# RELAY16.net
KiCad netlist of a schematic drawn in Altium Designer
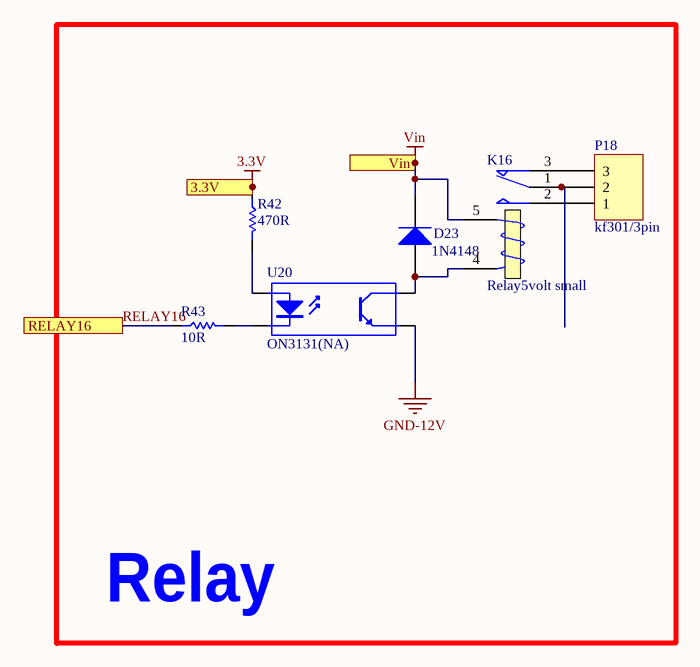
[diagram p0: RELAY16.SchDoc]

(export (version "E")
  (design (tool "Eeschema 10.0.6"))
  (components
    (comp (ref "D23")
      (value "1N4148")
      (footprint "sod123")
      (description "1 Amp General Purpose Rectifier")
      (fields (field (name "PUBLISHER") "Altium Limited"))
      (libsource (lib "Miscellaneous Devices") (part "Diode 1N4007"))
    )
    (comp (ref "K16")
      (value "Relay5volt small")
      (footprint "relay5_childern")
      (description "SPDT Relay")
      (fields (field (name "PUBLISHER") "Altium Limited"))
      (libsource (lib "FLIB") (part "Relay"))
    )
    (comp (ref "P18")
      (value "kf301/3pin")
      (footprint "Blue Connector 1*3 -kf301")
      (fields (field (name "PUBLISHER") "Altium Limited"))
      (libsource (lib "Miscellaneous Connectors") (part "Header 3"))
    )
    (comp (ref "R42")
      (value "470R")
      (footprint "0805/resistor")
      (description "Resistor")
      (fields (field (name "TOLERANCE") "5%") (field (name "POWER") "1/8 W"))
      (libsource (lib "skille") (part "Resistor"))
    )
    (comp (ref "R43")
      (value "10R")
      (footprint "0805/resistor")
      (description "Resistor")
      (fields (field (name "TOLERANCE") "5%") (field (name "POWER") "1/8 W"))
      (libsource (lib "skille") (part "Resistor"))
    )
    (comp (ref "U20")
      (value "ON3131(NA)")
      (footprint "OPTO_COUPLER")
      (description "4-Pin Phototransistor Optocoupler")
      (fields (field (name "PUBLISHER") "Altium Limited"))
      (libsource (lib "skille") (part "Optoisolator1"))
    )
  )
  (nets
    (net (code "1") (name "/RELAY16") (class "Default")
      (node (ref "R43") (pin "1") (pinfunction "1_1") (pintype "passive"))
    )
    (net (code "2") (name "3.3V") (class "Default")
      (node (ref "R42") (pin "1") (pinfunction "1_1") (pintype "passive"))
    )
    (net (code "3") (name "GND-12V") (class "Default")
      (node (ref "U20") (pin "3") (pinfunction "E_3") (pintype "passive"))
    )
    (net (code "4") (name "Net-(K16-COM)") (class "Default")
      (node (ref "K16") (pin "1") (pinfunction "COM_1") (pintype "passive"))
      (node (ref "P18") (pin "2") (pinfunction "2_2") (pintype "passive"))
    )
    (net (code "5") (name "Net-(K16-NO)") (class "Default")
      (node (ref "K16") (pin "2") (pinfunction "NO_2") (pintype "passive"))
      (node (ref "P18") (pin "1") (pinfunction "1_1") (pintype "passive"))
    )
    (net (code "6") (name "Net-(K16-T1)") (class "Default")
      (node (ref "K16") (pin "3") (pinfunction "T1_3") (pintype "passive"))
      (node (ref "P18") (pin "3") (pinfunction "3_3") (pintype "passive"))
    )
    (net (code "7") (name "Net-(K16-T2)") (class "Default")
      (node (ref "D23") (pin "A") (pinfunction "A_A") (pintype "passive"))
      (node (ref "K16") (pin "4") (pinfunction "T2_4") (pintype "passive"))
      (node (ref "U20") (pin "4") (pinfunction "C_4") (pintype "passive"))
    )
    (net (code "8") (name "Net-(U20-A)") (class "Default")
      (node (ref "R42") (pin "2") (pinfunction "2_2") (pintype "passive"))
      (node (ref "U20") (pin "1") (pinfunction "A_1") (pintype "passive"))
    )
    (net (code "9") (name "Net-(U20-K)") (class "Default")
      (node (ref "R43") (pin "2") (pinfunction "2_2") (pintype "passive"))
      (node (ref "U20") (pin "2") (pinfunction "K_2") (pintype "passive"))
    )
    (net (code "10") (name "Vin") (class "Default")
      (node (ref "D23") (pin "K") (pinfunction "K_K") (pintype "passive"))
      (node (ref "K16") (pin "5") (pinfunction "5_5") (pintype "passive"))
    )
  )
)
